# schematic_diagram.net
KiCad netlist of a schematic drawn in Altium Designer
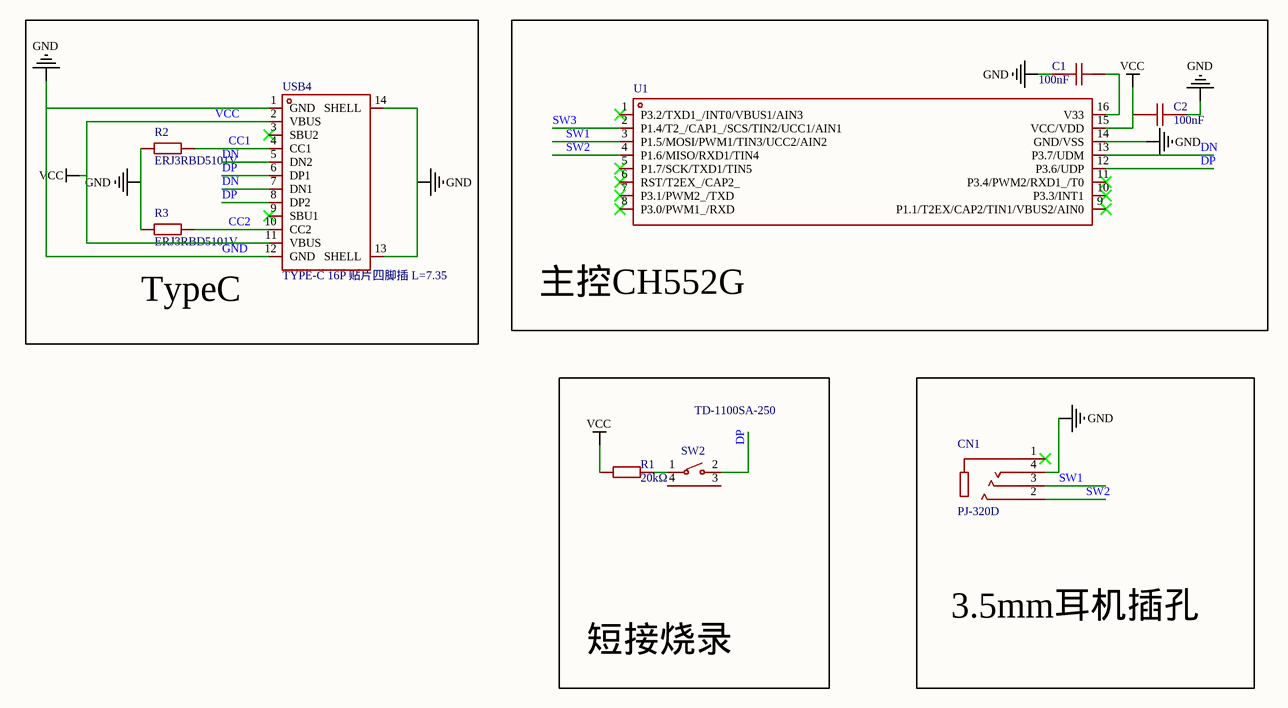
[diagram p0: schematic diagram.schdoc]

(export (version "E")
  (design (tool "Eeschema 10.0.6"))
  (components
    (comp (ref "C1")
      (value "100nF")
      (footprint "C0603")
      (description "容值:100nF;精度:±10%;额定电压:50V;材质(温度系数):X7R;")
      (fields
        (field (name "MANUFACTURER") "YAGEO(国巨)")
        (field (name "MANUFACTURER PART") "CC0603KRX7R9BB104")
      )
      (libsource (lib "altium-import") (part "root_0_CC0603KRX7R9BB104_"))
    )
    (comp (ref "C2")
      (value "100nF")
      (footprint "C0603")
      (description "容值:100nF;精度:±10%;额定电压:50V;材质(温度系数):X7R;")
      (fields
        (field (name "MANUFACTURER") "YAGEO(国巨)")
        (field (name "MANUFACTURER PART") "CC0603KRX7R9BB104")
      )
      (libsource (lib "altium-import") (part "root_0_CC0603KRX7R9BB104_"))
    )
    (comp (ref "CN1")
      (value "PJ-320D")
      (footprint "AUDIO-SMD_PJ-320D")
      (description "连接器类型:3.5mm耳机座;额定电流:300mA;额定电压:50V;工作温度范围:-16℃~+65℃;")
      (fields (field (name "MANUFACTURER") "SHOU HAN(首韩)"))
      (libsource (lib "altium-import") (part "root_0_PJ-320D_C431535_"))
    )
    (comp (ref "R1")
      (value "20kΩ")
      (footprint "R0603")
      (description "电阻类型:厚膜电阻;阻值:20kΩ;精度:±1%;功率:100mW;温度系数:±100ppm/;最大工作电压:75V;工作温度范围:-55~+155;")
      (fields
        (field (name "MANUFACTURER") "UNI-ROYAL(厚声)")
        (field (name "MANUFACTURER PART") "0603WAF2002T5E")
      )
      (libsource (lib "altium-import") (part "root_2_0603WAF2002T5E_"))
    )
    (comp (ref "R2")
      (value "ERJ3RBD5101V")
      (footprint "R0603")
      (fields (field (name "MANUFACTURER") "PANASONIC(松下)"))
      (libsource (lib "altium-import") (part "root_0_ERJ3RBD5101V_"))
    )
    (comp (ref "R3")
      (value "ERJ3RBD5101V")
      (footprint "R0603")
      (fields (field (name "MANUFACTURER") "PANASONIC(松下)"))
      (libsource (lib "altium-import") (part "root_0_ERJ3RBD5101V_"))
    )
    (comp (ref "SW2")
      (value "TD-1100SA-250")
      (footprint "SW-SMD_TD-1100SA-250")
      (fields (field (name "MANUFACTURER") "DEALON(德艺隆)"))
      (libsource (lib "altium-import") (part "root_0_TD-1100SA-250_"))
    )
    (comp (ref "U1")
      (value "CH552G")
      (footprint "SOP-16_L10.0-W3.9-P1.27-LS6.0-BL")
      (fields (field (name "MANUFACTURER") "WCH(南京沁恒)"))
      (libsource (lib "altium-import") (part "root_0_CH552G_"))
    )
    (comp (ref "USB4")
      (value "TYPE-C 16P 贴片四脚插 L=7.35")
      (footprint "USB-C-SMD_TYPE-C-6PIN-2MD-073")
      (libsource (lib "altium-import") (part "root_0_TYPE-C 16P 贴片四脚插 L=7.35_"))
    )
  )
  (nets
    (net (code "1") (name "/CC1") (class "Default")
      (node (ref "R2") (pin "2") (pinfunction "2_2") (pintype "passive"))
      (node (ref "USB4") (pin "4") (pinfunction "CC1_4") (pintype "passive"))
    )
    (net (code "2") (name "/CC2") (class "Default")
      (node (ref "R3") (pin "2") (pinfunction "2_2") (pintype "passive"))
      (node (ref "USB4") (pin "10") (pinfunction "CC2_10") (pintype "passive"))
    )
    (net (code "3") (name "/DN") (class "Default")
      (node (ref "U1") (pin "13") (pinfunction "P3.7/UDM_13") (pintype "passive"))
      (node (ref "USB4") (pin "5") (pinfunction "DN2_5") (pintype "passive"))
      (node (ref "USB4") (pin "7") (pinfunction "DN1_7") (pintype "passive"))
    )
    (net (code "4") (name "/DP") (class "Default")
      (node (ref "SW2") (pin "2") (pinfunction "2_2") (pintype "passive"))
      (node (ref "U1") (pin "12") (pinfunction "P3.6/UDP_12") (pintype "passive"))
      (node (ref "USB4") (pin "6") (pinfunction "DP1_6") (pintype "passive"))
      (node (ref "USB4") (pin "8") (pinfunction "DP2_8") (pintype "passive"))
    )
    (net (code "5") (name "/SW1") (class "Default")
      (node (ref "CN1") (pin "3") (pinfunction "3_3") (pintype "passive"))
      (node (ref "U1") (pin "3") (pinfunction "P1.5/MOSI/PWM1/TIN3/UCC2/AIN2_3") (pintype "passive"))
    )
    (net (code "6") (name "/SW2") (class "Default")
      (node (ref "CN1") (pin "2") (pinfunction "2_2") (pintype "passive"))
      (node (ref "U1") (pin "4") (pinfunction "P1.6/MISO/RXD1/TIN4_4") (pintype "passive"))
    )
    (net (code "7") (name "/SW3") (class "Default")
      (node (ref "U1") (pin "2") (pinfunction "P1.4/T2_/CAP1_/SCS/TIN2/UCC1/AIN1_2") (pintype "passive"))
    )
    (net (code "8") (name "GND") (class "Default")
      (node (ref "C1") (pin "1") (pinfunction "1_1") (pintype "passive"))
      (node (ref "C2") (pin "2") (pinfunction "2_2") (pintype "passive"))
      (node (ref "CN1") (pin "4") (pinfunction "4_4") (pintype "passive"))
      (node (ref "R2") (pin "1") (pinfunction "1_1") (pintype "passive"))
      (node (ref "R3") (pin "1") (pinfunction "1_1") (pintype "passive"))
      (node (ref "U1") (pin "14") (pinfunction "GND/VSS_14") (pintype "passive"))
      (node (ref "USB4") (pin "1") (pinfunction "GND_1") (pintype "passive"))
      (node (ref "USB4") (pin "12") (pinfunction "GND_12") (pintype "passive"))
      (node (ref "USB4") (pin "13") (pinfunction "SHELL_13") (pintype "passive"))
      (node (ref "USB4") (pin "14") (pinfunction "SHELL_14") (pintype "passive"))
    )
    (net (code "9") (name "Net-(R1-Pad1)") (class "Default")
      (node (ref "R1") (pin "1") (pinfunction "1_1") (pintype "passive"))
      (node (ref "SW2") (pin "1") (pinfunction "1_1") (pintype "passive"))
    )
    (net (code "10") (name "Net-(U1-V33)") (class "Default")
      (node (ref "C1") (pin "2") (pinfunction "2_2") (pintype "passive"))
      (node (ref "U1") (pin "16") (pinfunction "V33_16") (pintype "passive"))
    )
    (net (code "11") (name "VCC") (class "Default")
      (node (ref "C2") (pin "1") (pinfunction "1_1") (pintype "passive"))
      (node (ref "R1") (pin "2") (pinfunction "2_2") (pintype "passive"))
      (node (ref "U1") (pin "15") (pinfunction "VCC/VDD_15") (pintype "passive"))
      (node (ref "USB4") (pin "11") (pinfunction "VBUS_11") (pintype "passive"))
      (node (ref "USB4") (pin "2") (pinfunction "VBUS_2") (pintype "passive"))
    )
    (net (code "12") (name "unconnected-(CN1-Pad1)") (class "Default")
      (node (ref "CN1") (pin "1") (pinfunction "1_1") (pintype "passive+no_connect"))
    )
    (net (code "13") (name "unconnected-(SW2-Pad3)") (class "Default")
      (node (ref "SW2") (pin "3") (pinfunction "3_3") (pintype "passive"))
    )
    (net (code "14") (name "unconnected-(SW2-Pad4)") (class "Default")
      (node (ref "SW2") (pin "4") (pinfunction "4_4") (pintype "passive"))
    )
    (net (code "15") (name "unconnected-(U1-P1.1{slash}T2EX{slash}CAP2{slash}TIN1{slash}VBUS2{slash}AIN0-Pad9)") (class "Default")
      (node (ref "U1") (pin "9") (pinfunction "P1.1/T2EX/CAP2/TIN1/VBUS2/AIN0_9") (pintype "passive+no_connect"))
    )
    (net (code "16") (name "unconnected-(U1-P1.7{slash}SCK{slash}TXD1{slash}TIN5-Pad5)") (class "Default")
      (node (ref "U1") (pin "5") (pinfunction "P1.7/SCK/TXD1/TIN5_5") (pintype "passive+no_connect"))
    )
    (net (code "17") (name "unconnected-(U1-P3.0{slash}PWM1_{slash}RXD-Pad8)") (class "Default")
      (node (ref "U1") (pin "8") (pinfunction "P3.0/PWM1_/RXD_8") (pintype "passive+no_connect"))
    )
    (net (code "18") (name "unconnected-(U1-P3.1{slash}PWM2_{slash}TXD-Pad7)") (class "Default")
      (node (ref "U1") (pin "7") (pinfunction "P3.1/PWM2_/TXD_7") (pintype "passive+no_connect"))
    )
    (net (code "19") (name "unconnected-(U1-P3.2{slash}TXD1_{slash}INT0{slash}VBUS1{slash}AIN3-Pad1)") (class "Default")
      (node (ref "U1") (pin "1") (pinfunction "P3.2/TXD1_/INT0/VBUS1/AIN3_1") (pintype "passive+no_connect"))
    )
    (net (code "20") (name "unconnected-(U1-P3.3{slash}INT1-Pad10)") (class "Default")
      (node (ref "U1") (pin "10") (pinfunction "P3.3/INT1_10") (pintype "passive+no_connect"))
    )
    (net (code "21") (name "unconnected-(U1-P3.4{slash}PWM2{slash}RXD1_{slash}T0-Pad11)") (class "Default")
      (node (ref "U1") (pin "11") (pinfunction "P3.4/PWM2/RXD1_/T0_11") (pintype "passive+no_connect"))
    )
    (net (code "22") (name "unconnected-(U1-RST{slash}T2EX_{slash}CAP2_-Pad6)") (class "Default")
      (node (ref "U1") (pin "6") (pinfunction "RST/T2EX_/CAP2__6") (pintype "passive+no_connect"))
    )
    (net (code "23") (name "unconnected-(USB4-SBU1-Pad9)") (class "Default")
      (node (ref "USB4") (pin "9") (pinfunction "SBU1_9") (pintype "passive+no_connect"))
    )
    (net (code "24") (name "unconnected-(USB4-SBU2-Pad3)") (class "Default")
      (node (ref "USB4") (pin "3") (pinfunction "SBU2_3") (pintype "passive+no_connect"))
    )
  )
)
